# Vapeix_mini_power.net
KiCad netlist of a schematic drawn in Altium Designer
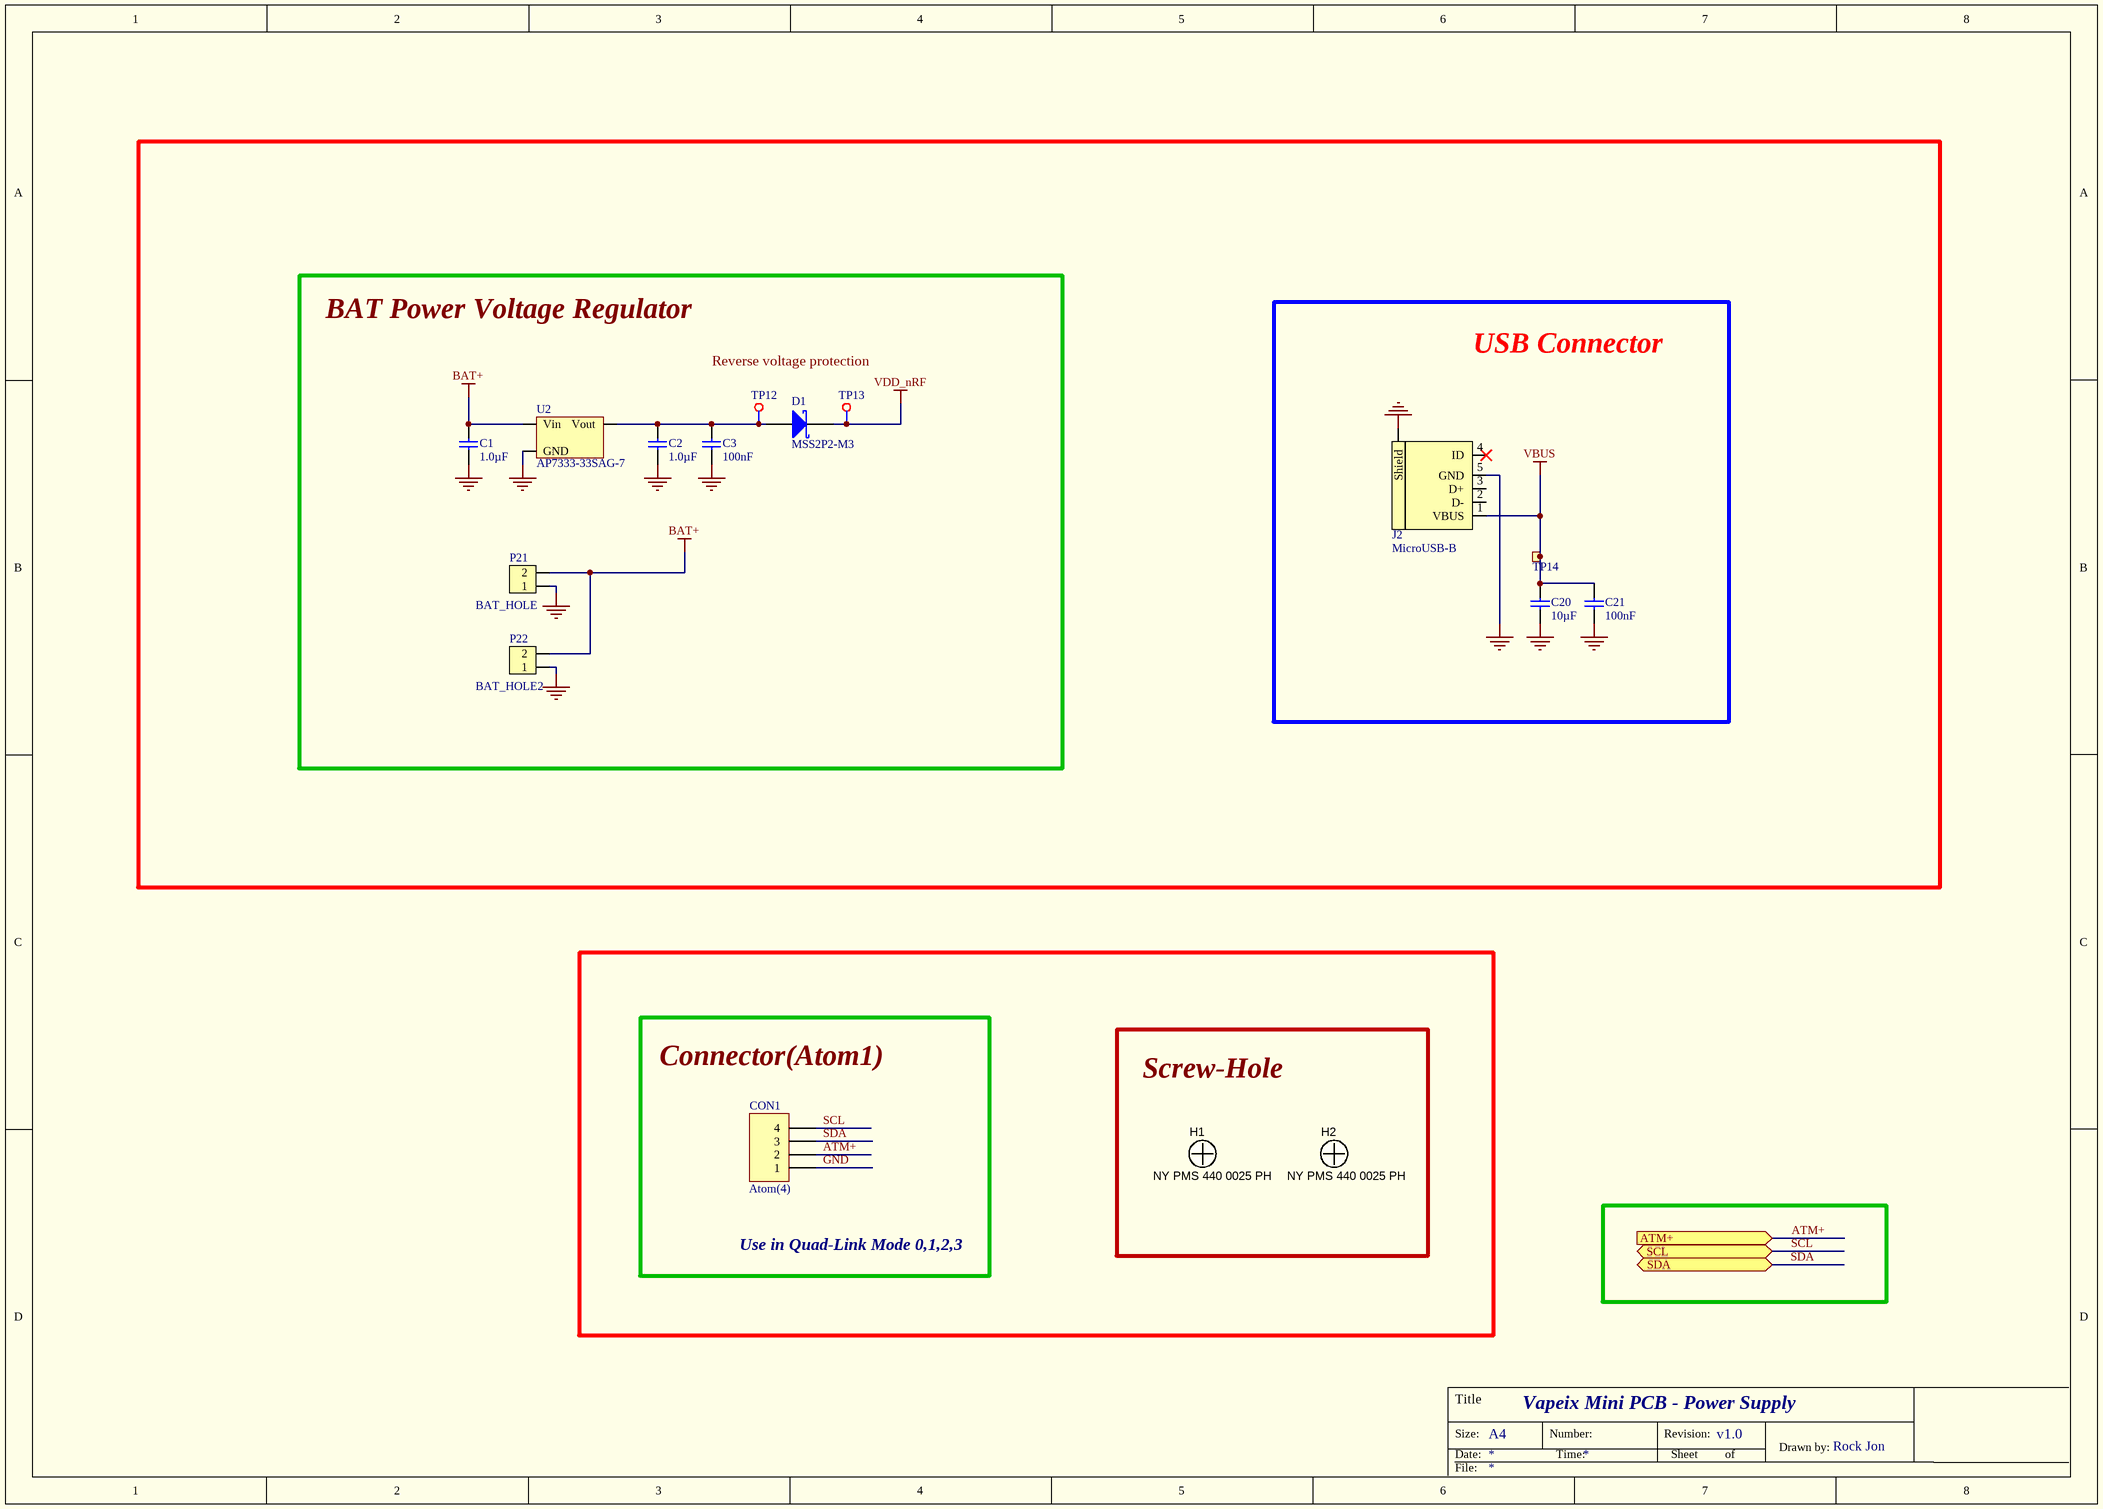
[diagram p0: Vapeix_mini_power.SchDoc]

(export (version "E")
  (design (tool "Eeschema 10.0.6"))
  (components
    (comp (ref "C1")
      (value "1.0µF")
      (footprint "C0201")
      (description "Capacitor, X7R, ±10%")
      (fields (field (name "PART NUMBER") "C0603-1µ0") (field (name "PUBLISHER") "Nordic Semiconductor"))
      (libsource (lib "Nordic Passive DB") (part "CAP"))
    )
    (comp (ref "C2")
      (value "1.0µF")
      (footprint "C0201")
      (description "Capacitor, X7R, ±10%")
      (fields (field (name "PART NUMBER") "C0603-1µ0") (field (name "PUBLISHER") "Nordic Semiconductor"))
      (libsource (lib "Nordic Passive DB") (part "CAP"))
    )
    (comp (ref "C3")
      (value "100nF")
      (footprint "C0201")
      (description "Capacitor, X7R, ±10%")
      (fields (field (name "PART NUMBER") "C0402-100n") (field (name "PUBLISHER") "Nordic Semiconductor"))
      (libsource (lib "Nordic Passive DB") (part "CAP"))
    )
    (comp (ref "C20")
      (value "10µF")
      (footprint "C0201")
      (description "Capacitor, X5R, ±20%")
      (fields (field (name "PART NUMBER") "C0603-10µ") (field (name "PUBLISHER") "Nordic Semiconductor"))
      (libsource (lib "Nordic Passive DB") (part "CAP"))
    )
    (comp (ref "C21")
      (value "100nF")
      (footprint "C0201")
      (description "Capacitor, X7R, ±10%")
      (fields (field (name "PART NUMBER") "C0402-100n") (field (name "PUBLISHER") "Nordic Semiconductor"))
      (libsource (lib "Nordic Passive DB") (part "CAP"))
    )
    (comp (ref "CON1")
      (value "Atom(4)")
      (footprint "S4B-PH-K-S")
      (description "CONN HEADER PH SIDE 4POS 2MM")
      (fields
        (field (name "MANUFACTURER") "JST Sales America Inc.")
        (field (name "MANUFACTURER PART NUMBER") "S4B-PH-K-S(LF)(SN)")
      )
      (libsource (lib "VapeixS_LIB") (part "S4B-PH-K-S(LF)(SN)"))
    )
    (comp (ref "D1")
      (value "MSS2P2-M3")
      (footprint "MSS2P2-M3")
      (description "DIODE SCHOTTKY 20V 2A MICROSMP")
      (fields
        (field (name "MANUFACTURER") "Vishay Semiconductor Diodes Division")
        (field (name "MANUFACTURER PART NUMBER") "MSS2P2-M3/89A")
      )
      (libsource (lib "VapeixS_LIB") (part "MSS2P2-M3/89A"))
    )
    (comp (ref "H1")
      (value "NY PMS 440 0025 PH")
      (footprint "SCREW_HOLE2")
      (description "Machine Screw, Round, #4-40 x 1/4, Nylon, Philips panhead")
      (fields
        (field (name "MANUFACTURER") "B&F Fastener Supply")
        (field (name "DIGIKEYPARTNUMBER") "H542-ND")
        (field (name "SYMBOLCREATOR") "codlsc")
        (field (name "PUBLISHER") "Texas Instruments")
      )
      (libsource (lib "VapeixS_LIB") (part "Screw-Hole"))
    )
    (comp (ref "H2")
      (value "NY PMS 440 0025 PH")
      (footprint "SCREW_HOLE2")
      (description "Machine Screw, Round, #4-40 x 1/4, Nylon, Philips panhead")
      (fields
        (field (name "MANUFACTURER") "B&F Fastener Supply")
        (field (name "DIGIKEYPARTNUMBER") "H542-ND")
        (field (name "SYMBOLCREATOR") "codlsc")
        (field (name "PUBLISHER") "Texas Instruments")
      )
      (libsource (lib "VapeixS_LIB") (part "Screw-Hole"))
    )
    (comp (ref "J2")
      (value "MicroUSB-B")
      (footprint "FCI_10118193-0001LF")
      (description "MicroUSB-B-SMT")
      (fields
        (field (name "PART NUMBER") "FCI 10118193-0001LF")
        (field (name "MANUFACTURER") "FCI")
        (field (name "PUBLISHER") "Nordic Semiconductor")
      )
      (libsource (lib "Nordic Passive DB") (part "MiniUSB-AB-SMT"))
    )
    (comp (ref "P21")
      (value "BAT_HOLE")
      (footprint "CON2")
      (description "Pin List 1x2, 2.54mm (100mil), Right Angled, SMD")
      (fields
        (field (name "PART NUMBER") "Pin List Ang 1x2 SMD, 2.54mm")
        (field (name "2ND SOURCE PART NUMBER") "S1113E-02-ND")
        (field (name "PUBLISHER") "Nordic Semiconductor")
      )
      (libsource (lib "Nordic Passive DB") (part "CONN-2"))
    )
    (comp (ref "P22")
      (value "BAT_HOLE2")
      (footprint "CON2")
      (description "Pin List 1x2, 2.54mm (100mil), Right Angled, SMD")
      (fields
        (field (name "PART NUMBER") "Pin List Ang 1x2 SMD, 2.54mm")
        (field (name "2ND SOURCE PART NUMBER") "S1113E-02-ND")
        (field (name "PUBLISHER") "Nordic Semiconductor")
      )
      (libsource (lib "Nordic Passive DB") (part "CONN-2"))
    )
    (comp (ref "TP12")
      (value "TP")
      (footprint "TP")
      (description "TEST POINT")
      (libsource (lib "VapeixS_LIB") (part "TP"))
    )
    (comp (ref "TP13")
      (value "TP")
      (footprint "TP")
      (description "TEST POINT")
      (libsource (lib "VapeixS_LIB") (part "TP"))
    )
    (comp (ref "TP14")
      (value "Ø1.0mm,SMD")
      (footprint "TP_SMD_Ø1.0mm")
      (description "1.0mm circular SMD testpad")
      (fields
        (field (name "PART NUMBER") "TP_SMD_Ø1.0MM")
        (field (name "MANUFACTURER") "Nordic Semiconductor")
        (field (name "PUBLISHER") "Nordic Semiconductor")
      )
      (libsource (lib "Nordic Passive DB") (part "TESTPAD"))
    )
    (comp (ref "U2")
      (value "AP7333-33SAG-7")
      (footprint "SOT-23A")
      (description "300mA, Low Quiescent Current, Fast Transient Low Dropout Linear Regulator")
      (fields
        (field (name "MANUFACTURER") "Diodes Incorporated")
        (field (name "PUBLISHER") "Nordic Semiconductor")
      )
      (libsource (lib "Nordic Active DB") (part "AP7333-XXSAG"))
    )
  )
  (nets
    (net (code "1") (name "/ATM+") (class "Default")
      (node (ref "CON1") (pin "2") (pinfunction "2_2") (pintype "passive"))
    )
    (net (code "4") (name "/SCL") (class "Default")
      (node (ref "CON1") (pin "4") (pinfunction "4_4") (pintype "passive"))
    )
    (net (code "5") (name "/SDA") (class "Default")
      (node (ref "CON1") (pin "3") (pinfunction "3_3") (pintype "passive"))
    )
    (net (code "9") (name "BAT+") (class "Default")
      (node (ref "C1") (pin "2") (pinfunction "2_2") (pintype "passive"))
      (node (ref "P21") (pin "2") (pinfunction "2_2") (pintype "passive"))
      (node (ref "P22") (pin "2") (pinfunction "2_2") (pintype "passive"))
      (node (ref "U2") (pin "1") (pinfunction "Vin_1") (pintype "passive"))
    )
    (net (code "10") (name "GND") (class "Default")
      (node (ref "C1") (pin "1") (pinfunction "1_1") (pintype "passive"))
      (node (ref "C2") (pin "1") (pinfunction "1_1") (pintype "passive"))
      (node (ref "C20") (pin "1") (pinfunction "1_1") (pintype "passive"))
      (node (ref "C21") (pin "1") (pinfunction "1_1") (pintype "passive"))
      (node (ref "C3") (pin "1") (pinfunction "1_1") (pintype "passive"))
      (node (ref "CON1") (pin "1") (pinfunction "1_1") (pintype "passive"))
      (node (ref "J2") (pin "5") (pinfunction "GND_5") (pintype "power_in"))
      (node (ref "J2") (pin "6") (pinfunction "Shield_6") (pintype "power_in"))
      (node (ref "P21") (pin "1") (pinfunction "1_1") (pintype "passive"))
      (node (ref "P22") (pin "1") (pinfunction "1_1") (pintype "passive"))
      (node (ref "U2") (pin "3") (pinfunction "GND_3") (pintype "passive"))
    )
    (net (code "11") (name "Net-(D1-A)") (class "Default")
      (node (ref "C2") (pin "2") (pinfunction "2_2") (pintype "passive"))
      (node (ref "C3") (pin "2") (pinfunction "2_2") (pintype "passive"))
      (node (ref "D1") (pin "1") (pinfunction "A_1") (pintype "passive"))
      (node (ref "TP12") (pin "1") (pinfunction "TP_1") (pintype "passive"))
      (node (ref "U2") (pin "2") (pinfunction "Vout_2") (pintype "passive"))
    )
    (net (code "12") (name "VBUS") (class "Default")
      (node (ref "C20") (pin "2") (pinfunction "2_2") (pintype "passive"))
      (node (ref "C21") (pin "2") (pinfunction "2_2") (pintype "passive"))
      (node (ref "J2") (pin "1") (pinfunction "VBUS_1") (pintype "power_in"))
      (node (ref "TP14") (pin "1") (pinfunction "1_1") (pintype "passive"))
    )
    (net (code "13") (name "VDD_nRF") (class "Default")
      (node (ref "D1") (pin "2") (pinfunction "K_2") (pintype "passive"))
      (node (ref "TP13") (pin "1") (pinfunction "TP_1") (pintype "passive"))
    )
    (net (code "14") (name "unconnected-(J2-D+-Pad3)") (class "Default")
      (node (ref "J2") (pin "3") (pinfunction "D+_3") (pintype "passive"))
    )
    (net (code "15") (name "unconnected-(J2-D--Pad2)") (class "Default")
      (node (ref "J2") (pin "2") (pinfunction "D-_2") (pintype "passive"))
    )
    (net (code "16") (name "unconnected-(J2-ID-Pad4)") (class "Default")
      (node (ref "J2") (pin "4") (pinfunction "ID_4") (pintype "passive+no_connect"))
    )
  )
)
